# Sch_Dr_PWR5V.net
KiCad netlist of a schematic drawn in Altium Designer
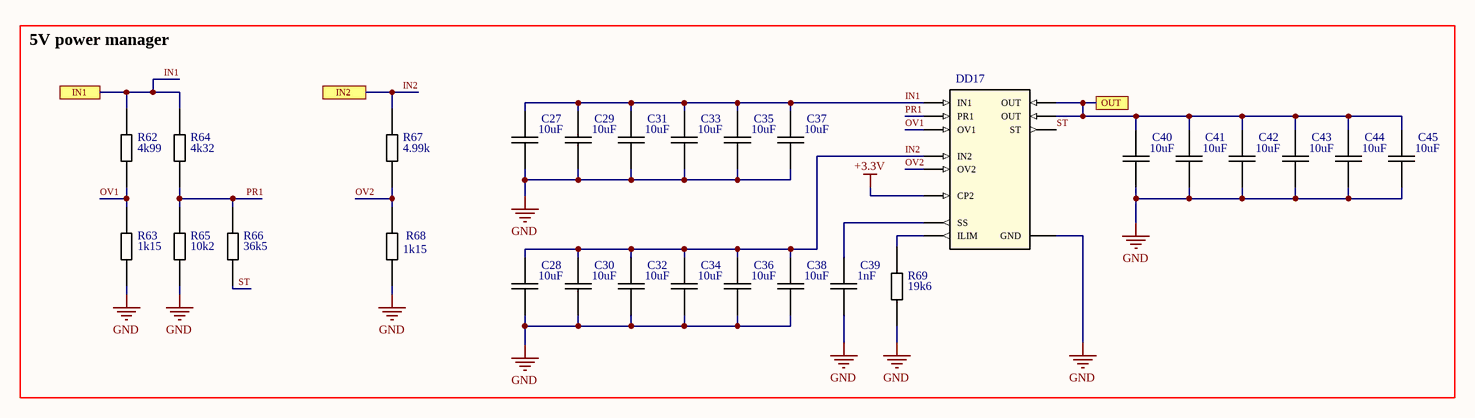
[diagram p0: Sch_Dr_PWR5V .SchDoc]

(export (version "E")
  (design (tool "Eeschema 10.0.6"))
  (components
    (comp (ref "C27")
      (value "10uF")
      (footprint "Cap_0603")
      (description "CC0603KRX5R7BB106")
      (libsource (lib "Dr_lib") (part "Cap_"))
    )
    (comp (ref "C28")
      (value "10uF")
      (footprint "Cap_0603")
      (description "CC0603KRX5R7BB106")
      (libsource (lib "Dr_lib") (part "Cap_"))
    )
    (comp (ref "C29")
      (value "10uF")
      (footprint "Cap_0603")
      (description "CC0603KRX5R7BB106")
      (libsource (lib "Dr_lib") (part "Cap_"))
    )
    (comp (ref "C30")
      (value "10uF")
      (footprint "Cap_0603")
      (description "CC0603KRX5R7BB106")
      (libsource (lib "Dr_lib") (part "Cap_"))
    )
    (comp (ref "C31")
      (value "10uF")
      (footprint "Cap_0603")
      (description "CC0603KRX5R7BB106")
      (libsource (lib "Dr_lib") (part "Cap_"))
    )
    (comp (ref "C32")
      (value "10uF")
      (footprint "Cap_0603")
      (description "CC0603KRX5R7BB106")
      (libsource (lib "Dr_lib") (part "Cap_"))
    )
    (comp (ref "C33")
      (value "10uF")
      (footprint "Cap_0603")
      (description "CC0603KRX5R7BB106")
      (libsource (lib "Dr_lib") (part "Cap_"))
    )
    (comp (ref "C34")
      (value "10uF")
      (footprint "Cap_0603")
      (description "CC0603KRX5R7BB106")
      (libsource (lib "Dr_lib") (part "Cap_"))
    )
    (comp (ref "C35")
      (value "10uF")
      (footprint "Cap_0603")
      (description "CC0603KRX5R7BB106")
      (libsource (lib "Dr_lib") (part "Cap_"))
    )
    (comp (ref "C36")
      (value "10uF")
      (footprint "Cap_0603")
      (description "CC0603KRX5R7BB106")
      (libsource (lib "Dr_lib") (part "Cap_"))
    )
    (comp (ref "C37")
      (value "10uF")
      (footprint "Cap_0603")
      (description "CC0603KRX5R7BB106")
      (libsource (lib "Dr_lib") (part "Cap_"))
    )
    (comp (ref "C38")
      (value "10uF")
      (footprint "Cap_0603")
      (description "CC0603KRX5R7BB106")
      (libsource (lib "Dr_lib") (part "Cap_"))
    )
    (comp (ref "C39")
      (value "1nF")
      (footprint "Cap_0603")
      (description "CC0603JRX7R9BB102")
      (libsource (lib "Dr_lib") (part "Cap_"))
    )
    (comp (ref "C40")
      (value "10uF")
      (footprint "Cap_0603")
      (description "CC0603KRX5R7BB106")
      (libsource (lib "Dr_lib") (part "Cap_"))
    )
    (comp (ref "C41")
      (value "10uF")
      (footprint "Cap_0603")
      (description "CC0603KRX5R7BB106")
      (libsource (lib "Dr_lib") (part "Cap_"))
    )
    (comp (ref "C42")
      (value "10uF")
      (footprint "Cap_0603")
      (description "CC0603KRX5R7BB106")
      (libsource (lib "Dr_lib") (part "Cap_"))
    )
    (comp (ref "C43")
      (value "10uF")
      (footprint "Cap_0603")
      (description "CC0603KRX5R7BB106")
      (libsource (lib "") (part "Cap__1"))
    )
    (comp (ref "C44")
      (value "10uF")
      (footprint "Cap_0603")
      (description "CC0603KRX5R7BB106")
      (libsource (lib "Dr_lib") (part "Cap_"))
    )
    (comp (ref "C45")
      (value "10uF")
      (footprint "Cap_0603")
      (description "CC0603KRX5R7BB106")
      (libsource (lib "Dr_lib") (part "Cap_"))
    )
    (comp (ref "DD17")
      (value "TPS2121RUXR")
      (footprint "12-pin VQFN-HR")
      (description "2.8V to 22V Priority Power MUX with Seamless Switchover")
      (libsource (lib "Dr_lib") (part "TPS2121RUXR"))
    )
    (comp (ref "R62")
      (value "4k99")
      (footprint "Res_0603")
      (description "RC0603FR-074K99L")
      (libsource (lib "Dr_lib") (part "Res_"))
    )
    (comp (ref "R63")
      (value "1k15")
      (footprint "Res_0603")
      (description "RC0603FR-071K15L")
      (libsource (lib "Dr_lib") (part "Res_"))
    )
    (comp (ref "R64")
      (value "4k32")
      (footprint "Res_0603")
      (description "RC0603FR-074K32L")
      (libsource (lib "Dr_lib") (part "Res_"))
    )
    (comp (ref "R65")
      (value "10k2")
      (footprint "Res_0603")
      (description "RC0603FR-0710K2L")
      (libsource (lib "Dr_lib") (part "Res_"))
    )
    (comp (ref "R66")
      (value "36k5")
      (footprint "Res_0603")
      (description "RC0603FR-0736K5L")
      (libsource (lib "Dr_lib") (part "Res_"))
    )
    (comp (ref "R67")
      (value "4.99k")
      (footprint "Res_0603")
      (description "RC0603FR-074K99L")
      (libsource (lib "Dr_lib") (part "Res_"))
    )
    (comp (ref "R68")
      (value "1k15")
      (footprint "Res_0603")
      (description "RC0603FR-071K15L")
      (libsource (lib "Dr_lib") (part "Res_"))
    )
    (comp (ref "R69")
      (value "19k6")
      (footprint "Res_0603")
      (description "RC0603FR-0719K6L")
      (libsource (lib "Dr_lib") (part "Res_"))
    )
  )
  (nets
    (net (code "1") (name "+3.3V") (class "Default")
      (node (ref "DD17") (pin "3") (pinfunction "CP2_3") (pintype "input"))
    )
    (net (code "2") (name "/IN1") (class "Default")
      (node (ref "C27") (pin "2") (pinfunction "2_2") (pintype "passive"))
      (node (ref "C29") (pin "2") (pinfunction "2_2") (pintype "passive"))
      (node (ref "C31") (pin "2") (pinfunction "2_2") (pintype "passive"))
      (node (ref "C33") (pin "2") (pinfunction "2_2") (pintype "passive"))
      (node (ref "C35") (pin "2") (pinfunction "2_2") (pintype "passive"))
      (node (ref "C37") (pin "2") (pinfunction "2_2") (pintype "passive"))
      (node (ref "DD17") (pin "7") (pinfunction "IN1_7") (pintype "input"))
      (node (ref "R62") (pin "1") (pinfunction "1_1") (pintype "passive"))
      (node (ref "R64") (pin "1") (pinfunction "1_1") (pintype "passive"))
    )
    (net (code "3") (name "/IN2") (class "Default")
      (node (ref "C28") (pin "2") (pinfunction "2_2") (pintype "passive"))
      (node (ref "C30") (pin "2") (pinfunction "2_2") (pintype "passive"))
      (node (ref "C32") (pin "2") (pinfunction "2_2") (pintype "passive"))
      (node (ref "C34") (pin "2") (pinfunction "2_2") (pintype "passive"))
      (node (ref "C36") (pin "2") (pinfunction "2_2") (pintype "passive"))
      (node (ref "C38") (pin "2") (pinfunction "2_2") (pintype "passive"))
      (node (ref "DD17") (pin "2") (pinfunction "IN2_2") (pintype "input"))
      (node (ref "R67") (pin "1") (pinfunction "1_1") (pintype "passive"))
    )
    (net (code "4") (name "/OUT") (class "Default")
      (node (ref "C40") (pin "2") (pinfunction "2_2") (pintype "passive"))
      (node (ref "C41") (pin "2") (pinfunction "2_2") (pintype "passive"))
      (node (ref "C42") (pin "2") (pinfunction "2_2") (pintype "passive"))
      (node (ref "C43") (pin "2") (pinfunction "2_2") (pintype "passive"))
      (node (ref "C44") (pin "2") (pinfunction "2_2") (pintype "passive"))
      (node (ref "C45") (pin "2") (pinfunction "2_2") (pintype "passive"))
      (node (ref "DD17") (pin "1") (pinfunction "OUT_1") (pintype "input"))
      (node (ref "DD17") (pin "8") (pinfunction "OUT_8") (pintype "input"))
    )
    (net (code "5") (name "/OV1") (class "Default")
      (node (ref "DD17") (pin "5") (pinfunction "OV1_5") (pintype "input"))
      (node (ref "R62") (pin "2") (pinfunction "2_2") (pintype "passive"))
      (node (ref "R63") (pin "1") (pinfunction "1_1") (pintype "passive"))
    )
    (net (code "6") (name "/OV2") (class "Default")
      (node (ref "DD17") (pin "4") (pinfunction "OV2_4") (pintype "input"))
      (node (ref "R67") (pin "2") (pinfunction "2_2") (pintype "passive"))
      (node (ref "R68") (pin "1") (pinfunction "1_1") (pintype "passive"))
    )
    (net (code "7") (name "/PR1") (class "Default")
      (node (ref "DD17") (pin "6") (pinfunction "PR1_6") (pintype "input"))
      (node (ref "R64") (pin "2") (pinfunction "2_2") (pintype "passive"))
      (node (ref "R65") (pin "1") (pinfunction "1_1") (pintype "passive"))
      (node (ref "R66") (pin "1") (pinfunction "1_1") (pintype "passive"))
    )
    (net (code "8") (name "/ST") (class "Default")
      (node (ref "DD17") (pin "9") (pinfunction "ST_9") (pintype "output"))
      (node (ref "R66") (pin "2") (pinfunction "2_2") (pintype "passive"))
    )
    (net (code "9") (name "GND") (class "Default")
      (node (ref "C27") (pin "1") (pinfunction "1_1") (pintype "passive"))
      (node (ref "C28") (pin "1") (pinfunction "1_1") (pintype "passive"))
      (node (ref "C29") (pin "1") (pinfunction "1_1") (pintype "passive"))
      (node (ref "C30") (pin "1") (pinfunction "1_1") (pintype "passive"))
      (node (ref "C31") (pin "1") (pinfunction "1_1") (pintype "passive"))
      (node (ref "C32") (pin "1") (pinfunction "1_1") (pintype "passive"))
      (node (ref "C33") (pin "1") (pinfunction "1_1") (pintype "passive"))
      (node (ref "C34") (pin "1") (pinfunction "1_1") (pintype "passive"))
      (node (ref "C35") (pin "1") (pinfunction "1_1") (pintype "passive"))
      (node (ref "C36") (pin "1") (pinfunction "1_1") (pintype "passive"))
      (node (ref "C37") (pin "1") (pinfunction "1_1") (pintype "passive"))
      (node (ref "C38") (pin "1") (pinfunction "1_1") (pintype "passive"))
      (node (ref "C39") (pin "1") (pinfunction "1_1") (pintype "passive"))
      (node (ref "C40") (pin "1") (pinfunction "1_1") (pintype "passive"))
      (node (ref "C41") (pin "1") (pinfunction "1_1") (pintype "passive"))
      (node (ref "C42") (pin "1") (pinfunction "1_1") (pintype "passive"))
      (node (ref "C43") (pin "1") (pinfunction "1_1") (pintype "passive"))
      (node (ref "C44") (pin "1") (pinfunction "1_1") (pintype "passive"))
      (node (ref "C45") (pin "1") (pinfunction "1_1") (pintype "passive"))
      (node (ref "DD17") (pin "12") (pinfunction "GND_12") (pintype "passive"))
      (node (ref "R63") (pin "2") (pinfunction "2_2") (pintype "passive"))
      (node (ref "R65") (pin "2") (pinfunction "2_2") (pintype "passive"))
      (node (ref "R68") (pin "2") (pinfunction "2_2") (pintype "passive"))
      (node (ref "R69") (pin "2") (pinfunction "2_2") (pintype "passive"))
    )
    (net (code "10") (name "Net-(DD17-ILIM)") (class "Default")
      (node (ref "DD17") (pin "10") (pinfunction "ILIM_10") (pintype "output"))
      (node (ref "R69") (pin "1") (pinfunction "1_1") (pintype "passive"))
    )
    (net (code "11") (name "Net-(DD17-SS)") (class "Default")
      (node (ref "C39") (pin "2") (pinfunction "2_2") (pintype "passive"))
      (node (ref "DD17") (pin "11") (pinfunction "SS_11") (pintype "output"))
    )
  )
)
